# 15A.net
KiCad netlist of a schematic drawn in EasyEDA Pro
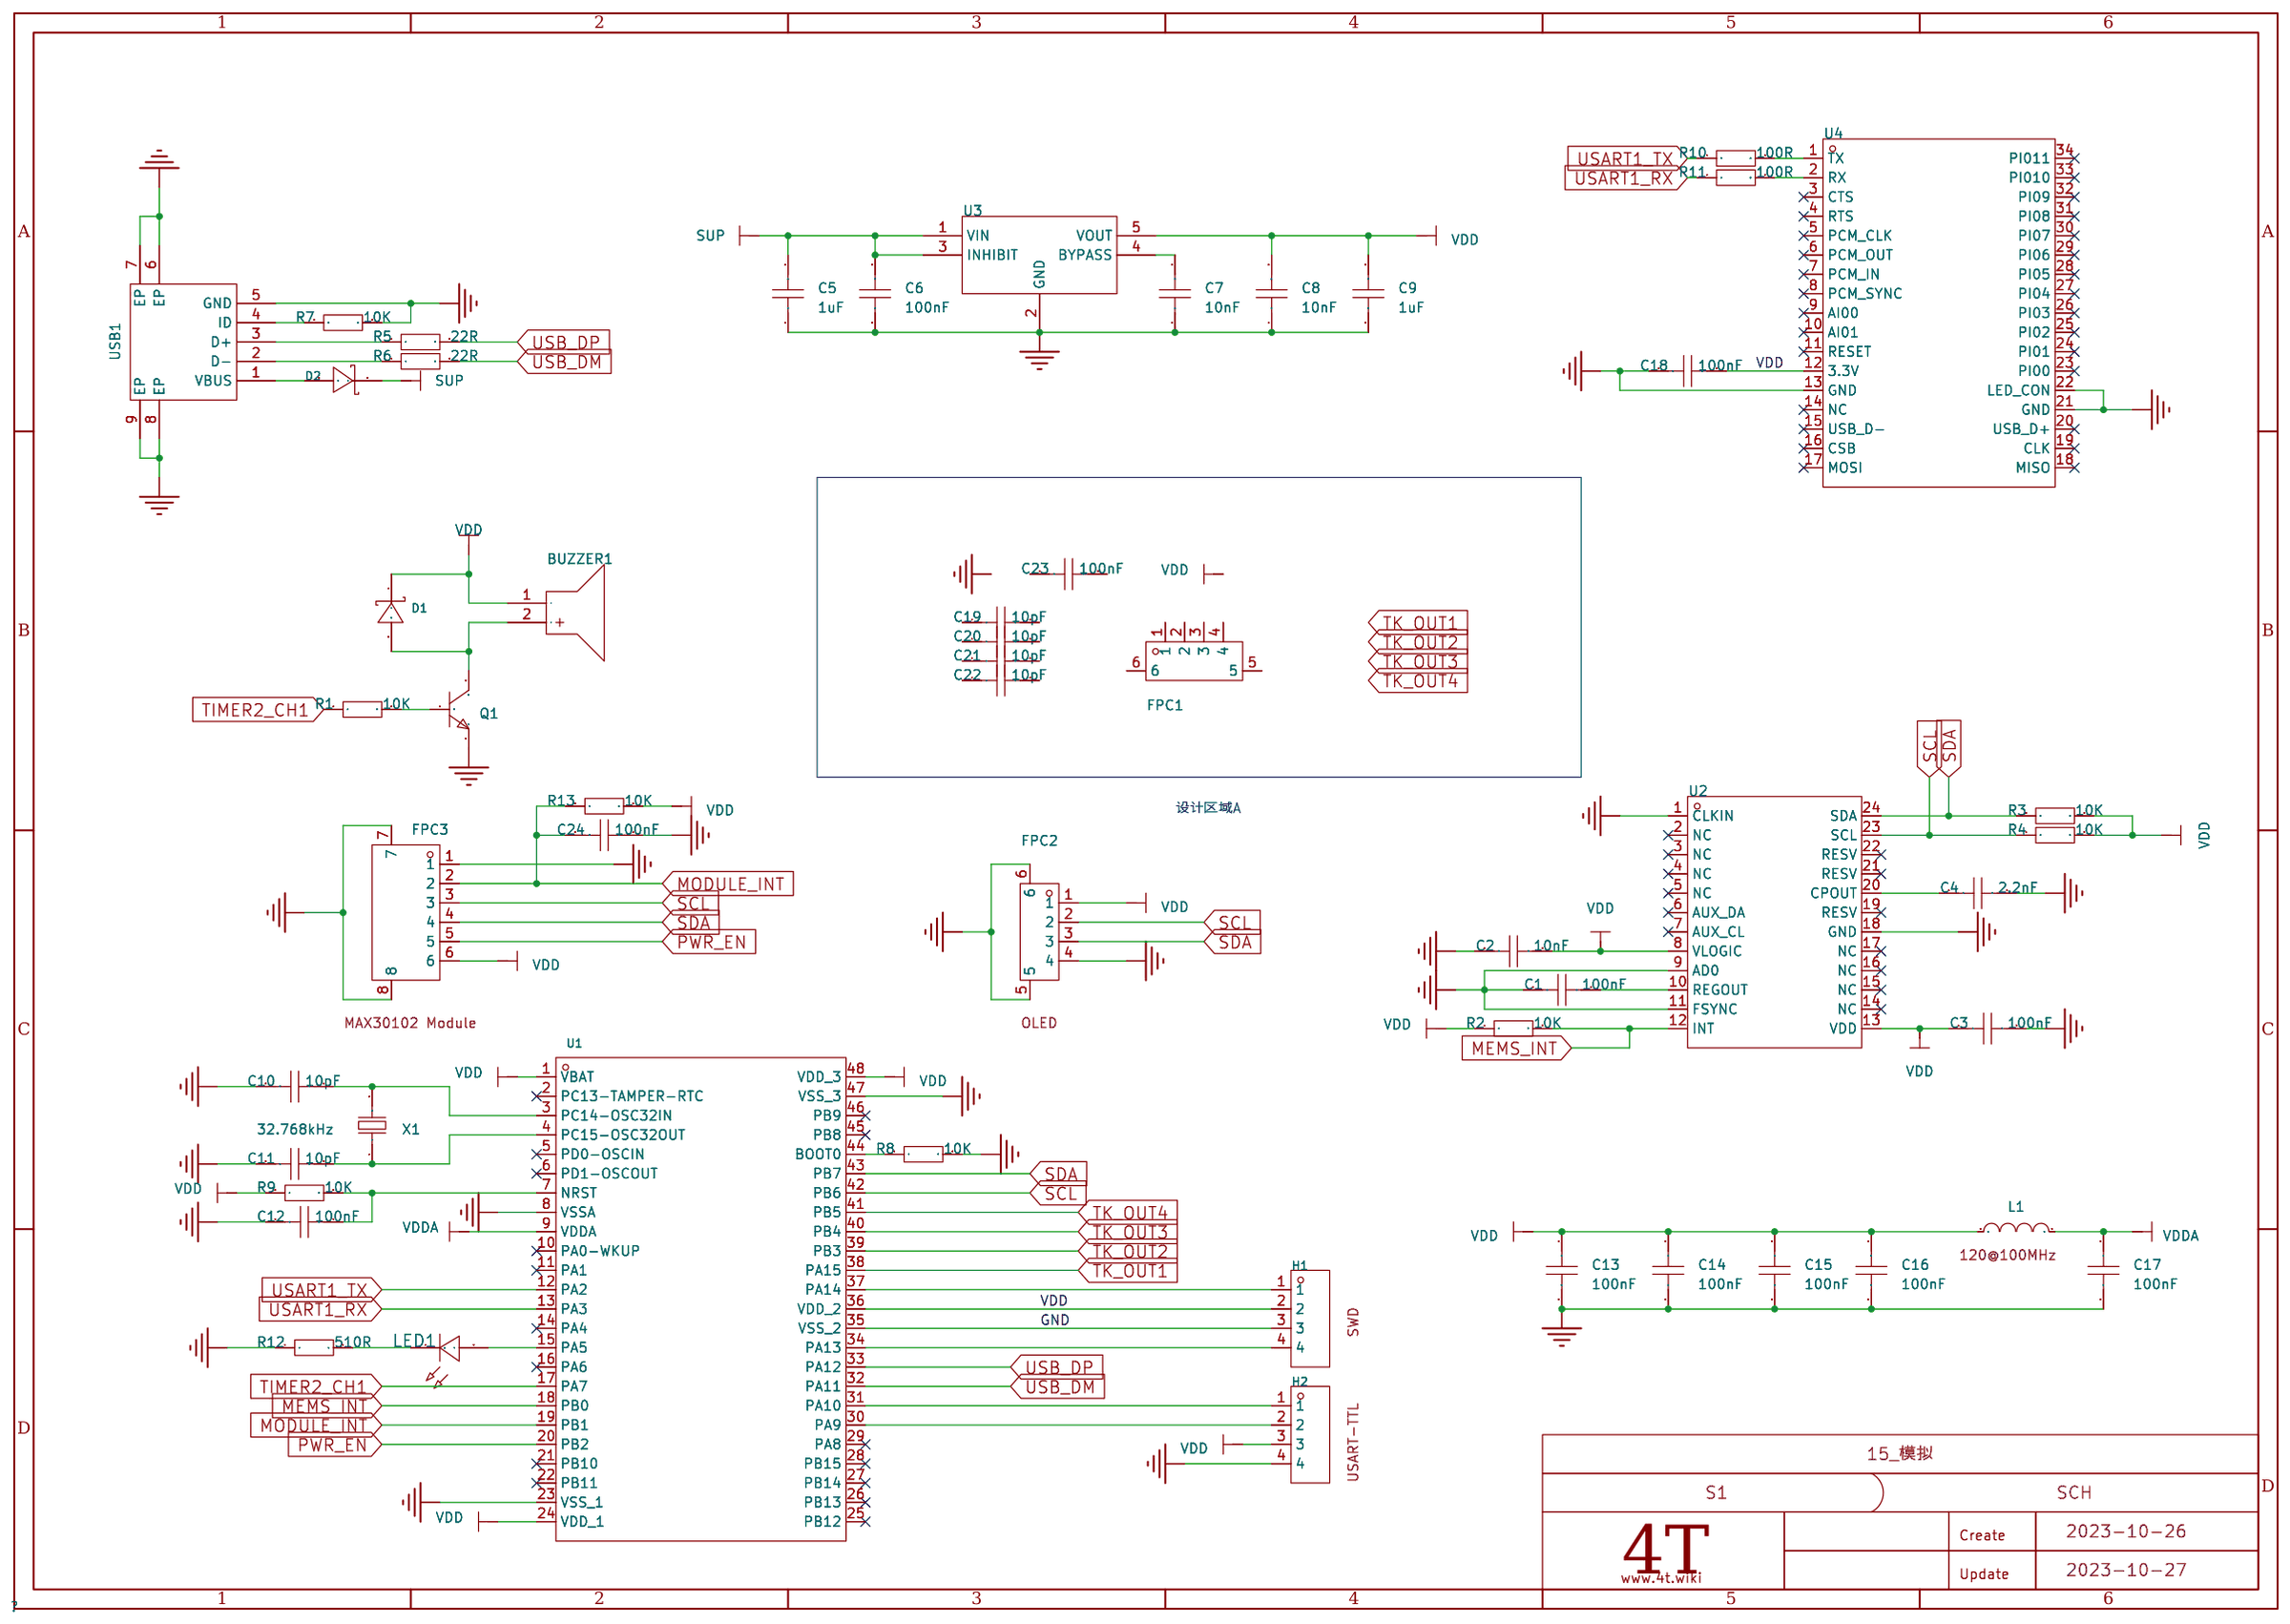
[diagram p0: schematic sheet]

(export (version "E")
  (design (tool "Eeschema 10.0.6"))
  (components
    (comp (ref "BUZZER1")
      (value "buzzer")
      (footprint "easyedapro:BUZ-TH_BD12.0-P6.00-D0.9-RD")
      (libsource (lib "easyedapro") (part "BUZZER"))
    )
    (comp (ref "C1")
      (value "100nF")
      (footprint "easyedapro:C0805")
      (libsource (lib "easyedapro") (part "CapAcitance"))
    )
    (comp (ref "C2")
      (value "10nF")
      (footprint "easyedapro:C0805")
      (libsource (lib "easyedapro") (part "CapAcitance"))
    )
    (comp (ref "C3")
      (value "100nF")
      (footprint "easyedapro:C0805")
      (libsource (lib "easyedapro") (part "CapAcitance"))
    )
    (comp (ref "C4")
      (value "2.2nF")
      (footprint "easyedapro:C0805")
      (libsource (lib "easyedapro") (part "CapAcitance"))
    )
    (comp (ref "C5")
      (value "1uF")
      (footprint "easyedapro:C0805")
      (libsource (lib "easyedapro") (part "CapAcitance"))
    )
    (comp (ref "C6")
      (value "100nF")
      (footprint "easyedapro:C0805")
      (libsource (lib "easyedapro") (part "CapAcitance"))
    )
    (comp (ref "C7")
      (value "10nF")
      (footprint "easyedapro:C0805")
      (libsource (lib "easyedapro") (part "CapAcitance"))
    )
    (comp (ref "C8")
      (value "10nF")
      (footprint "easyedapro:C0805")
      (libsource (lib "easyedapro") (part "CapAcitance"))
    )
    (comp (ref "C9")
      (value "1uF")
      (footprint "easyedapro:C0805")
      (libsource (lib "easyedapro") (part "CapAcitance"))
    )
    (comp (ref "C10")
      (value "10pF")
      (footprint "easyedapro:C0805")
      (libsource (lib "easyedapro") (part "CapAcitance"))
    )
    (comp (ref "C11")
      (value "10pF")
      (footprint "easyedapro:C0805")
      (libsource (lib "easyedapro") (part "CapAcitance"))
    )
    (comp (ref "C12")
      (value "100nF")
      (footprint "easyedapro:C0805")
      (libsource (lib "easyedapro") (part "CapAcitance"))
    )
    (comp (ref "C13")
      (value "100nF")
      (footprint "easyedapro:C0805")
      (libsource (lib "easyedapro") (part "CapAcitance"))
    )
    (comp (ref "C14")
      (value "100nF")
      (footprint "easyedapro:C0805")
      (libsource (lib "easyedapro") (part "CapAcitance"))
    )
    (comp (ref "C15")
      (value "100nF")
      (footprint "easyedapro:C0805")
      (libsource (lib "easyedapro") (part "CapAcitance"))
    )
    (comp (ref "C16")
      (value "100nF")
      (footprint "easyedapro:C0805")
      (libsource (lib "easyedapro") (part "CapAcitance"))
    )
    (comp (ref "C17")
      (value "100nF")
      (footprint "easyedapro:C0805")
      (libsource (lib "easyedapro") (part "CapAcitance"))
    )
    (comp (ref "C18")
      (value "100nF")
      (footprint "easyedapro:C0805")
      (libsource (lib "easyedapro") (part "CapAcitance"))
    )
    (comp (ref "C19")
      (value "10pF")
      (footprint "easyedapro:C0805")
      (libsource (lib "easyedapro") (part "CapAcitance"))
    )
    (comp (ref "C20")
      (value "10pF")
      (footprint "easyedapro:C0805")
      (libsource (lib "easyedapro") (part "CapAcitance"))
    )
    (comp (ref "C21")
      (value "10pF")
      (footprint "easyedapro:C0805")
      (libsource (lib "easyedapro") (part "CapAcitance"))
    )
    (comp (ref "C22")
      (value "10pF")
      (footprint "easyedapro:C0805")
      (libsource (lib "easyedapro") (part "CapAcitance"))
    )
    (comp (ref "C23")
      (value "100nF")
      (footprint "easyedapro:C0805")
      (libsource (lib "easyedapro") (part "CapAcitance"))
    )
    (comp (ref "C24")
      (value "100nF")
      (footprint "easyedapro:C0805")
      (libsource (lib "easyedapro") (part "CapAcitance"))
    )
    (comp (ref "D1")
      (value "SS14")
      (footprint "easyedapro:SMA_L4.2-W2.6-LS5.3-RD")
      (description "二极管配置:独立式;直流反向耐压(Vr):40V;平均整流电流(Io):1A;正向压降(Vf):550mV@1A;")
      (fields (field (name "Manufacturer") "MDD"))
      (libsource (lib "easyedapro") (part "SS14"))
    )
    (comp (ref "D2")
      (value "SS14")
      (footprint "easyedapro:SMA_L4.2-W2.6-LS5.3-RD")
      (description "二极管配置:独立式;直流反向耐压(Vr):40V;平均整流电流(Io):1A;正向压降(Vf):550mV@1A;")
      (fields (field (name "Manufacturer") "MDD"))
      (libsource (lib "easyedapro") (part "SS14"))
    )
    (comp (ref "FPC1")
      (value "FPC-4PIN-1.0MM-上接")
      (footprint "easyedapro:FPC-SMD_4P-P1.00_AFA07-S04ECC-00")
      (libsource (lib "easyedapro") (part "FPC-4PIN-1.0MM-上接"))
    )
    (comp (ref "FPC2")
      (value "FPC-4PIN-1.0MM-上接")
      (footprint "easyedapro:FPC-SMD_4P-P1.00_AFA07-S04ECC-00")
      (description "OLED")
      (libsource (lib "easyedapro") (part "FPC-4PIN-1.0MM-上接"))
    )
    (comp (ref "FPC3")
      (value "FPC6-0.5mm")
      (footprint "easyedapro:FPC-SMD_6P-L9.3-W4.1-P0.50")
      (description "MAX30102 Module")
      (libsource (lib "easyedapro") (part "FPC6-0.5MM"))
    )
    (comp (ref "H1")
      (value "~")
      (footprint "easyedapro:HDR-TH_4P-P2.54-V-F")
      (description "SWD")
      (libsource (lib "easyedapro") (part "2.54-1*4P母"))
    )
    (comp (ref "H2")
      (value "~")
      (footprint "easyedapro:HDR-TH_4P-P2.54-V-F")
      (description "USART-TTL")
      (libsource (lib "easyedapro") (part "2.54-1*4P母"))
    )
    (comp (ref "L1")
      (value "ACMS201209A6012A")
      (footprint "easyedapro:L0805")
      (description "120@100MHz")
      (fields (field (name "Manufacturer") "HYHONGYEX(宏业)"))
      (libsource (lib "easyedapro") (part "ACMS201209A6012A"))
    )
    (comp (ref "LED1")
      (value "~")
      (footprint "easyedapro:LED_0805")
      (libsource (lib "easyedapro") (part "LED_R"))
    )
    (comp (ref "Q1")
      (value "S8050")
      (footprint "easyedapro:SOT-23-3_L2.9-W1.3-P1.90-LS2.4-BR")
      (description "NPN 25V 500mA 120-400 SOT-23")
      (fields (field (name "Manufacturer") "Doeshare(德芯)"))
      (libsource (lib "easyedapro") (part "S8050_C2931719"))
    )
    (comp (ref "R1") (value "10K") (footprint "easyedapro:R0805") (libsource (lib "easyedapro") (part "电阻")))
    (comp (ref "R2") (value "10K") (footprint "easyedapro:R0805") (libsource (lib "easyedapro") (part "电阻")))
    (comp (ref "R3") (value "10K") (footprint "easyedapro:R0805") (libsource (lib "easyedapro") (part "电阻")))
    (comp (ref "R4") (value "10K") (footprint "easyedapro:R0805") (libsource (lib "easyedapro") (part "电阻")))
    (comp (ref "R5") (value "22R") (footprint "easyedapro:R0805") (libsource (lib "easyedapro") (part "电阻")))
    (comp (ref "R6") (value "22R") (footprint "easyedapro:R0805") (libsource (lib "easyedapro") (part "电阻")))
    (comp (ref "R7") (value "10K") (footprint "easyedapro:R0805") (libsource (lib "easyedapro") (part "电阻")))
    (comp (ref "R8") (value "10K") (footprint "easyedapro:R0805") (libsource (lib "easyedapro") (part "电阻")))
    (comp (ref "R9") (value "10K") (footprint "easyedapro:R0805") (libsource (lib "easyedapro") (part "电阻")))
    (comp (ref "R10")
      (value "100R")
      (footprint "easyedapro:R0805")
      (libsource (lib "easyedapro") (part "电阻"))
    )
    (comp (ref "R11")
      (value "100R")
      (footprint "easyedapro:R0805")
      (libsource (lib "easyedapro") (part "电阻"))
    )
    (comp (ref "R12")
      (value "510R")
      (footprint "easyedapro:R0805")
      (libsource (lib "easyedapro") (part "电阻"))
    )
    (comp (ref "R13") (value "10K") (footprint "easyedapro:R0805") (libsource (lib "easyedapro") (part "电阻")))
    (comp (ref "U1")
      (value "GD32F303CBT6")
      (footprint "easyedapro:LQFP-48_L7.0-W7.0-P0.50-LS9.0-BL")
      (libsource (lib "easyedapro") (part "GD32F303CBT6_C3013781"))
    )
    (comp (ref "U2")
      (value "MPU6050")
      (footprint "easyedapro:QFN-24_L4.0-W4.0-P0.50-BL")
      (libsource (lib "easyedapro") (part "MPU6050_C9900042518"))
    )
    (comp (ref "U3")
      (value "LD3985M33R")
      (footprint "easyedapro:SOT-23-5_L3.0-W1.7-P0.95-LS2.8-BR")
      (description "输出类型:固定;输出极性:正;最大输入电压:6V;输出电压:3.3V;输出电流:150mA;电源纹波抑制比(PSRR):60dB;")
      (fields (field (name "Manufacturer") "ST(意法半导体)"))
      (libsource (lib "easyedapro") (part "LD3985M33R"))
    )
    (comp (ref "U4")
      (value "HC-05")
      (footprint "easyedapro:BULETM-SMD_HC-05")
      (libsource (lib "easyedapro") (part "HC-05"))
    )
    (comp (ref "USB1")
      (value "MicroUSB-5PIN")
      (footprint "easyedapro:USB-SMD_5P_MICROUSB-5PIN")
      (libsource (lib "easyedapro") (part "MICROUSB-5PIN"))
    )
    (comp (ref "X1")
      (value "32.768kHz")
      (footprint "easyedapro:FC-135R_L3.2-W1.5")
      (description "频率:32.768kHz;频率公差:±20ppm;负载电容:12.5pF;")
      (fields (field (name "Manufacturer Part") "Q13FC1350000400") (field (name "Manufacturer") "EPSON(爱普生)"))
      (libsource (lib "easyedapro") (part "Q13FC1350000400"))
    )
  )
  (nets
    (net (code "1") (name "GND") (class "Default")
      (node (ref "C1") (pin "1") (pinfunction "1_1") (pintype "input"))
      (node (ref "C10") (pin "2") (pinfunction "2_2") (pintype "input"))
      (node (ref "C11") (pin "2") (pinfunction "2_2") (pintype "input"))
      (node (ref "C12") (pin "2") (pinfunction "2_2") (pintype "input"))
      (node (ref "C13") (pin "2") (pinfunction "2_2") (pintype "input"))
      (node (ref "C14") (pin "2") (pinfunction "2_2") (pintype "input"))
      (node (ref "C15") (pin "2") (pinfunction "2_2") (pintype "input"))
      (node (ref "C16") (pin "2") (pinfunction "2_2") (pintype "input"))
      (node (ref "C17") (pin "2") (pinfunction "2_2") (pintype "input"))
      (node (ref "C18") (pin "1") (pinfunction "1_1") (pintype "input"))
      (node (ref "C2") (pin "1") (pinfunction "1_1") (pintype "input"))
      (node (ref "C24") (pin "1") (pinfunction "1_1") (pintype "input"))
      (node (ref "C3") (pin "2") (pinfunction "2_2") (pintype "input"))
      (node (ref "C4") (pin "2") (pinfunction "2_2") (pintype "input"))
      (node (ref "C5") (pin "1") (pinfunction "1_1") (pintype "input"))
      (node (ref "C6") (pin "1") (pinfunction "1_1") (pintype "input"))
      (node (ref "C7") (pin "1") (pinfunction "1_1") (pintype "input"))
      (node (ref "C8") (pin "1") (pinfunction "1_1") (pintype "input"))
      (node (ref "C9") (pin "1") (pinfunction "1_1") (pintype "input"))
      (node (ref "FPC2") (pin "4") (pinfunction "4_4") (pintype "input"))
      (node (ref "FPC2") (pin "5") (pinfunction "5_5") (pintype "input"))
      (node (ref "FPC2") (pin "6") (pinfunction "6_6") (pintype "input"))
      (node (ref "FPC3") (pin "1") (pinfunction "1_1") (pintype "input"))
      (node (ref "FPC3") (pin "7") (pinfunction "7_7") (pintype "input"))
      (node (ref "FPC3") (pin "8") (pinfunction "8_8") (pintype "input"))
      (node (ref "H1") (pin "3") (pinfunction "3_3") (pintype "input"))
      (node (ref "H2") (pin "4") (pinfunction "4_4") (pintype "input"))
      (node (ref "Q1") (pin "2") (pinfunction "E_2") (pintype "input"))
      (node (ref "R12") (pin "1") (pinfunction "1_1") (pintype "input"))
      (node (ref "R7") (pin "2") (pinfunction "2_2") (pintype "input"))
      (node (ref "R8") (pin "2") (pinfunction "2_2") (pintype "input"))
      (node (ref "U1") (pin "23") (pinfunction "VSS_1_23") (pintype "input"))
      (node (ref "U1") (pin "35") (pinfunction "VSS_2_35") (pintype "input"))
      (node (ref "U1") (pin "47") (pinfunction "VSS_3_47") (pintype "input"))
      (node (ref "U1") (pin "8") (pinfunction "VSSA_8") (pintype "input"))
      (node (ref "U2") (pin "1") (pinfunction "CLKIN_1") (pintype "input"))
      (node (ref "U2") (pin "11") (pinfunction "FSYNC_11") (pintype "input"))
      (node (ref "U2") (pin "18") (pinfunction "GND_18") (pintype "input"))
      (node (ref "U2") (pin "9") (pinfunction "AD0_9") (pintype "input"))
      (node (ref "U3") (pin "2") (pinfunction "GND_2") (pintype "unspecified"))
      (node (ref "U4") (pin "13") (pinfunction "GND_13") (pintype "input"))
      (node (ref "U4") (pin "21") (pinfunction "GND_21") (pintype "input"))
      (node (ref "U4") (pin "22") (pinfunction "LED_CON_22") (pintype "input"))
      (node (ref "USB1") (pin "5") (pinfunction "GND_5") (pintype "input"))
      (node (ref "USB1") (pin "6") (pinfunction "EP_6") (pintype "input"))
      (node (ref "USB1") (pin "7") (pinfunction "EP_7") (pintype "input"))
      (node (ref "USB1") (pin "8") (pinfunction "EP_8") (pintype "input"))
      (node (ref "USB1") (pin "9") (pinfunction "EP_9") (pintype "input"))
    )
    (net (code "2") (name "MEMS_INT") (class "Default")
      (node (ref "R2") (pin "2") (pinfunction "2_2") (pintype "input"))
      (node (ref "U1") (pin "18") (pinfunction "PB0_18") (pintype "input"))
      (node (ref "U2") (pin "12") (pinfunction "INT_12") (pintype "input"))
    )
    (net (code "3") (name "MODULE_INT") (class "Default")
      (node (ref "C24") (pin "2") (pinfunction "2_2") (pintype "input"))
      (node (ref "FPC3") (pin "2") (pinfunction "2_2") (pintype "input"))
      (node (ref "R13") (pin "1") (pinfunction "1_1") (pintype "input"))
      (node (ref "U1") (pin "19") (pinfunction "PB1_19") (pintype "input"))
    )
    (net (code "4") (name "Net-(BUZZER1-+)") (class "Default")
      (node (ref "BUZZER1") (pin "2") (pinfunction "+_2") (pintype "input"))
      (node (ref "D1") (pin "2") (pinfunction "A_2") (pintype "input"))
      (node (ref "Q1") (pin "3") (pinfunction "C_3") (pintype "input"))
    )
    (net (code "5") (name "Net-(D2-A)") (class "Default")
      (node (ref "D2") (pin "2") (pinfunction "A_2") (pintype "input"))
      (node (ref "USB1") (pin "1") (pinfunction "VBUS_1") (pintype "input"))
    )
    (net (code "6") (name "Net-(LED1-A)") (class "Default")
      (node (ref "LED1") (pin "2") (pinfunction "A_2") (pintype "input"))
      (node (ref "U1") (pin "15") (pinfunction "PA5_15") (pintype "input"))
    )
    (net (code "7") (name "Net-(LED1-C)") (class "Default")
      (node (ref "LED1") (pin "1") (pinfunction "C_1") (pintype "input"))
      (node (ref "R12") (pin "2") (pinfunction "2_2") (pintype "input"))
    )
    (net (code "8") (name "Net-(Q1-B)") (class "Default")
      (node (ref "Q1") (pin "1") (pinfunction "B_1") (pintype "input"))
      (node (ref "R1") (pin "2") (pinfunction "2_2") (pintype "input"))
    )
    (net (code "9") (name "Net-(U1-BOOT0)") (class "Default")
      (node (ref "R8") (pin "1") (pinfunction "1_1") (pintype "input"))
      (node (ref "U1") (pin "44") (pinfunction "BOOT0_44") (pintype "input"))
    )
    (net (code "10") (name "Net-(U1-NRST)") (class "Default")
      (node (ref "C12") (pin "1") (pinfunction "1_1") (pintype "input"))
      (node (ref "R9") (pin "2") (pinfunction "2_2") (pintype "input"))
      (node (ref "U1") (pin "7") (pinfunction "NRST_7") (pintype "input"))
    )
    (net (code "11") (name "Net-(U1-PA9)") (class "Default")
      (node (ref "H2") (pin "2") (pinfunction "2_2") (pintype "input"))
      (node (ref "U1") (pin "30") (pinfunction "PA9_30") (pintype "input"))
    )
    (net (code "12") (name "Net-(U1-PA10)") (class "Default")
      (node (ref "H2") (pin "1") (pinfunction "1_1") (pintype "input"))
      (node (ref "U1") (pin "31") (pinfunction "PA10_31") (pintype "input"))
    )
    (net (code "13") (name "Net-(U1-PA13)") (class "Default")
      (node (ref "H1") (pin "4") (pinfunction "4_4") (pintype "input"))
      (node (ref "U1") (pin "34") (pinfunction "PA13_34") (pintype "input"))
    )
    (net (code "14") (name "Net-(U1-PA14)") (class "Default")
      (node (ref "H1") (pin "1") (pinfunction "1_1") (pintype "input"))
      (node (ref "U1") (pin "37") (pinfunction "PA14_37") (pintype "input"))
    )
    (net (code "15") (name "Net-(U1-PC14-OSC32IN)") (class "Default")
      (node (ref "C10") (pin "1") (pinfunction "1_1") (pintype "input"))
      (node (ref "U1") (pin "3") (pinfunction "PC14-OSC32IN_3") (pintype "input"))
      (node (ref "X1") (pin "2") (pinfunction "2_2") (pintype "input"))
    )
    (net (code "16") (name "Net-(U1-PC15-OSC32OUT)") (class "Default")
      (node (ref "C11") (pin "1") (pinfunction "1_1") (pintype "input"))
      (node (ref "U1") (pin "4") (pinfunction "PC15-OSC32OUT_4") (pintype "input"))
      (node (ref "X1") (pin "1") (pinfunction "1_1") (pintype "input"))
    )
    (net (code "17") (name "Net-(U2-CPOUT)") (class "Default")
      (node (ref "C4") (pin "1") (pinfunction "1_1") (pintype "input"))
      (node (ref "U2") (pin "20") (pinfunction "CPOUT_20") (pintype "input"))
    )
    (net (code "18") (name "Net-(U2-REGOUT)") (class "Default")
      (node (ref "C1") (pin "2") (pinfunction "2_2") (pintype "input"))
      (node (ref "U2") (pin "10") (pinfunction "REGOUT_10") (pintype "input"))
    )
    (net (code "19") (name "Net-(U3-BYPASS)") (class "Default")
      (node (ref "C7") (pin "2") (pinfunction "2_2") (pintype "input"))
      (node (ref "U3") (pin "4") (pinfunction "BYPASS_4") (pintype "unspecified"))
    )
    (net (code "20") (name "Net-(U4-RX)") (class "Default")
      (node (ref "R11") (pin "2") (pinfunction "2_2") (pintype "input"))
      (node (ref "U4") (pin "2") (pinfunction "RX_2") (pintype "input"))
    )
    (net (code "21") (name "Net-(U4-TX)") (class "Default")
      (node (ref "R10") (pin "2") (pinfunction "2_2") (pintype "input"))
      (node (ref "U4") (pin "1") (pinfunction "TX_1") (pintype "input"))
    )
    (net (code "22") (name "Net-(USB1-D+)") (class "Default")
      (node (ref "R5") (pin "1") (pinfunction "1_1") (pintype "input"))
      (node (ref "USB1") (pin "3") (pinfunction "D+_3") (pintype "input"))
    )
    (net (code "23") (name "Net-(USB1-D-)") (class "Default")
      (node (ref "R6") (pin "1") (pinfunction "1_1") (pintype "input"))
      (node (ref "USB1") (pin "2") (pinfunction "D-_2") (pintype "input"))
    )
    (net (code "24") (name "Net-(USB1-ID)") (class "Default")
      (node (ref "R7") (pin "1") (pinfunction "1_1") (pintype "input"))
      (node (ref "USB1") (pin "4") (pinfunction "ID_4") (pintype "input"))
    )
    (net (code "25") (name "PWR_EN") (class "Default")
      (node (ref "FPC3") (pin "5") (pinfunction "5_5") (pintype "input"))
      (node (ref "U1") (pin "20") (pinfunction "PB2_20") (pintype "input"))
    )
    (net (code "26") (name "SCL") (class "Default")
      (node (ref "FPC2") (pin "2") (pinfunction "2_2") (pintype "input"))
      (node (ref "FPC3") (pin "3") (pinfunction "3_3") (pintype "input"))
      (node (ref "R4") (pin "1") (pinfunction "1_1") (pintype "input"))
      (node (ref "U1") (pin "42") (pinfunction "PB6_42") (pintype "input"))
      (node (ref "U2") (pin "23") (pinfunction "SCL_23") (pintype "input"))
    )
    (net (code "27") (name "SDA") (class "Default")
      (node (ref "FPC2") (pin "3") (pinfunction "3_3") (pintype "input"))
      (node (ref "FPC3") (pin "4") (pinfunction "4_4") (pintype "input"))
      (node (ref "R3") (pin "1") (pinfunction "1_1") (pintype "input"))
      (node (ref "U1") (pin "43") (pinfunction "PB7_43") (pintype "input"))
      (node (ref "U2") (pin "24") (pinfunction "SDA_24") (pintype "input"))
    )
    (net (code "28") (name "SUP") (class "Default")
      (node (ref "C5") (pin "2") (pinfunction "2_2") (pintype "input"))
      (node (ref "C6") (pin "2") (pinfunction "2_2") (pintype "input"))
      (node (ref "D2") (pin "1") (pinfunction "K_1") (pintype "input"))
      (node (ref "U3") (pin "1") (pinfunction "VIN_1") (pintype "unspecified"))
      (node (ref "U3") (pin "3") (pinfunction "INHIBIT_3") (pintype "unspecified"))
    )
    (net (code "29") (name "TIMER2_CH1") (class "Default")
      (node (ref "R1") (pin "1") (pinfunction "1_1") (pintype "input"))
      (node (ref "U1") (pin "17") (pinfunction "PA7_17") (pintype "input"))
    )
    (net (code "30") (name "TK_OUT1") (class "Default")
      (node (ref "U1") (pin "38") (pinfunction "PA15_38") (pintype "input"))
    )
    (net (code "31") (name "TK_OUT2") (class "Default")
      (node (ref "U1") (pin "39") (pinfunction "PB3_39") (pintype "input"))
    )
    (net (code "32") (name "TK_OUT3") (class "Default")
      (node (ref "U1") (pin "40") (pinfunction "PB4_40") (pintype "input"))
    )
    (net (code "33") (name "TK_OUT4") (class "Default")
      (node (ref "U1") (pin "41") (pinfunction "PB5_41") (pintype "input"))
    )
    (net (code "34") (name "USART1_RX") (class "Default")
      (node (ref "R11") (pin "1") (pinfunction "1_1") (pintype "input"))
      (node (ref "U1") (pin "13") (pinfunction "PA3_13") (pintype "input"))
    )
    (net (code "35") (name "USART1_TX") (class "Default")
      (node (ref "R10") (pin "1") (pinfunction "1_1") (pintype "input"))
      (node (ref "U1") (pin "12") (pinfunction "PA2_12") (pintype "input"))
    )
    (net (code "36") (name "USB_DM") (class "Default")
      (node (ref "R6") (pin "2") (pinfunction "2_2") (pintype "input"))
      (node (ref "U1") (pin "32") (pinfunction "PA11_32") (pintype "input"))
    )
    (net (code "37") (name "USB_DP") (class "Default")
      (node (ref "R5") (pin "2") (pinfunction "2_2") (pintype "input"))
      (node (ref "U1") (pin "33") (pinfunction "PA12_33") (pintype "input"))
    )
    (net (code "38") (name "VDD") (class "Default")
      (node (ref "BUZZER1") (pin "1") (pinfunction "-_1") (pintype "input"))
      (node (ref "C13") (pin "1") (pinfunction "1_1") (pintype "input"))
      (node (ref "C14") (pin "1") (pinfunction "1_1") (pintype "input"))
      (node (ref "C15") (pin "1") (pinfunction "1_1") (pintype "input"))
      (node (ref "C16") (pin "1") (pinfunction "1_1") (pintype "input"))
      (node (ref "C18") (pin "2") (pinfunction "2_2") (pintype "input"))
      (node (ref "C2") (pin "2") (pinfunction "2_2") (pintype "input"))
      (node (ref "C3") (pin "1") (pinfunction "1_1") (pintype "input"))
      (node (ref "C8") (pin "2") (pinfunction "2_2") (pintype "input"))
      (node (ref "C9") (pin "2") (pinfunction "2_2") (pintype "input"))
      (node (ref "D1") (pin "1") (pinfunction "K_1") (pintype "input"))
      (node (ref "FPC2") (pin "1") (pinfunction "1_1") (pintype "input"))
      (node (ref "FPC3") (pin "6") (pinfunction "6_6") (pintype "input"))
      (node (ref "H1") (pin "2") (pinfunction "2_2") (pintype "input"))
      (node (ref "H2") (pin "3") (pinfunction "3_3") (pintype "input"))
      (node (ref "L1") (pin "1") (pinfunction "1_1") (pintype "input"))
      (node (ref "R13") (pin "2") (pinfunction "2_2") (pintype "input"))
      (node (ref "R2") (pin "1") (pinfunction "1_1") (pintype "input"))
      (node (ref "R3") (pin "2") (pinfunction "2_2") (pintype "input"))
      (node (ref "R4") (pin "2") (pinfunction "2_2") (pintype "input"))
      (node (ref "R9") (pin "1") (pinfunction "1_1") (pintype "input"))
      (node (ref "U1") (pin "1") (pinfunction "VBAT_1") (pintype "input"))
      (node (ref "U1") (pin "24") (pinfunction "VDD_1_24") (pintype "input"))
      (node (ref "U1") (pin "36") (pinfunction "VDD_2_36") (pintype "input"))
      (node (ref "U1") (pin "48") (pinfunction "VDD_3_48") (pintype "input"))
      (node (ref "U2") (pin "13") (pinfunction "VDD_13") (pintype "input"))
      (node (ref "U2") (pin "8") (pinfunction "VLOGIC_8") (pintype "input"))
      (node (ref "U3") (pin "5") (pinfunction "VOUT_5") (pintype "unspecified"))
      (node (ref "U4") (pin "12") (pinfunction "3.3V_12") (pintype "input"))
    )
    (net (code "39") (name "VDDA") (class "Default")
      (node (ref "C17") (pin "1") (pinfunction "1_1") (pintype "input"))
      (node (ref "L1") (pin "2") (pinfunction "2_2") (pintype "input"))
      (node (ref "U1") (pin "9") (pinfunction "VDDA_9") (pintype "input"))
    )
    (net (code "40") (name "unconnected-(C19-Pad1)") (class "Default")
      (node (ref "C19") (pin "1") (pinfunction "1_1") (pintype "input"))
    )
    (net (code "41") (name "unconnected-(C19-Pad2)") (class "Default")
      (node (ref "C19") (pin "2") (pinfunction "2_2") (pintype "input"))
    )
    (net (code "42") (name "unconnected-(C20-Pad1)") (class "Default")
      (node (ref "C20") (pin "1") (pinfunction "1_1") (pintype "input"))
    )
    (net (code "43") (name "unconnected-(C20-Pad2)") (class "Default")
      (node (ref "C20") (pin "2") (pinfunction "2_2") (pintype "input"))
    )
    (net (code "44") (name "unconnected-(C21-Pad1)") (class "Default")
      (node (ref "C21") (pin "1") (pinfunction "1_1") (pintype "input"))
    )
    (net (code "45") (name "unconnected-(C21-Pad2)") (class "Default")
      (node (ref "C21") (pin "2") (pinfunction "2_2") (pintype "input"))
    )
    (net (code "46") (name "unconnected-(C22-Pad1)") (class "Default")
      (node (ref "C22") (pin "1") (pinfunction "1_1") (pintype "input"))
    )
    (net (code "47") (name "unconnected-(C22-Pad2)") (class "Default")
      (node (ref "C22") (pin "2") (pinfunction "2_2") (pintype "input"))
    )
    (net (code "48") (name "unconnected-(C23-Pad1)") (class "Default")
      (node (ref "C23") (pin "1") (pinfunction "1_1") (pintype "input"))
    )
    (net (code "49") (name "unconnected-(C23-Pad2)") (class "Default")
      (node (ref "C23") (pin "2") (pinfunction "2_2") (pintype "input"))
    )
    (net (code "50") (name "unconnected-(FPC1-Pad1)") (class "Default")
      (node (ref "FPC1") (pin "1") (pinfunction "1_1") (pintype "input"))
    )
    (net (code "51") (name "unconnected-(FPC1-Pad2)") (class "Default")
      (node (ref "FPC1") (pin "2") (pinfunction "2_2") (pintype "input"))
    )
    (net (code "52") (name "unconnected-(FPC1-Pad3)") (class "Default")
      (node (ref "FPC1") (pin "3") (pinfunction "3_3") (pintype "input"))
    )
    (net (code "53") (name "unconnected-(FPC1-Pad4)") (class "Default")
      (node (ref "FPC1") (pin "4") (pinfunction "4_4") (pintype "input"))
    )
    (net (code "54") (name "unconnected-(FPC1-Pad5)") (class "Default")
      (node (ref "FPC1") (pin "5") (pinfunction "5_5") (pintype "input"))
    )
    (net (code "55") (name "unconnected-(FPC1-Pad6)") (class "Default")
      (node (ref "FPC1") (pin "6") (pinfunction "6_6") (pintype "input"))
    )
    (net (code "56") (name "unconnected-(U1-PA0-WKUP-Pad10)") (class "Default")
      (node (ref "U1") (pin "10") (pinfunction "PA0-WKUP_10") (pintype "input+no_connect"))
    )
    (net (code "57") (name "unconnected-(U1-PA1-Pad11)") (class "Default")
      (node (ref "U1") (pin "11") (pinfunction "PA1_11") (pintype "input+no_connect"))
    )
    (net (code "58") (name "unconnected-(U1-PA4-Pad14)") (class "Default")
      (node (ref "U1") (pin "14") (pinfunction "PA4_14") (pintype "input+no_connect"))
    )
    (net (code "59") (name "unconnected-(U1-PA6-Pad16)") (class "Default")
      (node (ref "U1") (pin "16") (pinfunction "PA6_16") (pintype "input+no_connect"))
    )
    (net (code "60") (name "unconnected-(U1-PA8-Pad29)") (class "Default")
      (node (ref "U1") (pin "29") (pinfunction "PA8_29") (pintype "input+no_connect"))
    )
    (net (code "61") (name "unconnected-(U1-PB8-Pad45)") (class "Default")
      (node (ref "U1") (pin "45") (pinfunction "PB8_45") (pintype "input+no_connect"))
    )
    (net (code "62") (name "unconnected-(U1-PB9-Pad46)") (class "Default")
      (node (ref "U1") (pin "46") (pinfunction "PB9_46") (pintype "input+no_connect"))
    )
    (net (code "63") (name "unconnected-(U1-PB10-Pad21)") (class "Default")
      (node (ref "U1") (pin "21") (pinfunction "PB10_21") (pintype "input+no_connect"))
    )
    (net (code "64") (name "unconnected-(U1-PB11-Pad22)") (class "Default")
      (node (ref "U1") (pin "22") (pinfunction "PB11_22") (pintype "input+no_connect"))
    )
    (net (code "65") (name "unconnected-(U1-PB12-Pad25)") (class "Default")
      (node (ref "U1") (pin "25") (pinfunction "PB12_25") (pintype "input+no_connect"))
    )
    (net (code "66") (name "unconnected-(U1-PB13-Pad26)") (class "Default")
      (node (ref "U1") (pin "26") (pinfunction "PB13_26") (pintype "input+no_connect"))
    )
    (net (code "67") (name "unconnected-(U1-PB14-Pad27)") (class "Default")
      (node (ref "U1") (pin "27") (pinfunction "PB14_27") (pintype "input+no_connect"))
    )
    (net (code "68") (name "unconnected-(U1-PB15-Pad28)") (class "Default")
      (node (ref "U1") (pin "28") (pinfunction "PB15_28") (pintype "input+no_connect"))
    )
    (net (code "69") (name "unconnected-(U1-PC13-TAMPER-RTC-Pad2)") (class "Default")
      (node (ref "U1") (pin "2") (pinfunction "PC13-TAMPER-RTC_2") (pintype "input+no_connect"))
    )
    (net (code "70") (name "unconnected-(U1-PD0-OSCIN-Pad5)") (class "Default")
      (node (ref "U1") (pin "5") (pinfunction "PD0-OSCIN_5") (pintype "input+no_connect"))
    )
    (net (code "71") (name "unconnected-(U1-PD1-OSCOUT-Pad6)") (class "Default")
      (node (ref "U1") (pin "6") (pinfunction "PD1-OSCOUT_6") (pintype "input+no_connect"))
    )
    (net (code "72") (name "unconnected-(U2-AUX_CL-Pad7)") (class "Default")
      (node (ref "U2") (pin "7") (pinfunction "AUX_CL_7") (pintype "input+no_connect"))
    )
    (net (code "73") (name "unconnected-(U2-AUX_DA-Pad6)") (class "Default")
      (node (ref "U2") (pin "6") (pinfunction "AUX_DA_6") (pintype "input+no_connect"))
    )
    (net (code "74") (name "unconnected-(U2-NC-Pad2)") (class "Default")
      (node (ref "U2") (pin "2") (pinfunction "NC_2") (pintype "input+no_connect"))
    )
    (net (code "75") (name "unconnected-(U2-NC-Pad3)") (class "Default")
      (node (ref "U2") (pin "3") (pinfunction "NC_3") (pintype "input+no_connect"))
    )
    (net (code "76") (name "unconnected-(U2-NC-Pad4)") (class "Default")
      (node (ref "U2") (pin "4") (pinfunction "NC_4") (pintype "input+no_connect"))
    )
    (net (code "77") (name "unconnected-(U2-NC-Pad5)") (class "Default")
      (node (ref "U2") (pin "5") (pinfunction "NC_5") (pintype "input+no_connect"))
    )
    (net (code "78") (name "unconnected-(U2-NC-Pad14)") (class "Default")
      (node (ref "U2") (pin "14") (pinfunction "NC_14") (pintype "input+no_connect"))
    )
    (net (code "79") (name "unconnected-(U2-NC-Pad15)") (class "Default")
      (node (ref "U2") (pin "15") (pinfunction "NC_15") (pintype "input+no_connect"))
    )
    (net (code "80") (name "unconnected-(U2-NC-Pad16)") (class "Default")
      (node (ref "U2") (pin "16") (pinfunction "NC_16") (pintype "input+no_connect"))
    )
    (net (code "81") (name "unconnected-(U2-NC-Pad17)") (class "Default")
      (node (ref "U2") (pin "17") (pinfunction "NC_17") (pintype "input+no_connect"))
    )
    (net (code "82") (name "unconnected-(U2-RESV-Pad19)") (class "Default")
      (node (ref "U2") (pin "19") (pinfunction "RESV_19") (pintype "input+no_connect"))
    )
    (net (code "83") (name "unconnected-(U2-RESV-Pad21)") (class "Default")
      (node (ref "U2") (pin "21") (pinfunction "RESV_21") (pintype "input+no_connect"))
    )
    (net (code "84") (name "unconnected-(U2-RESV-Pad22)") (class "Default")
      (node (ref "U2") (pin "22") (pinfunction "RESV_22") (pintype "input+no_connect"))
    )
    (net (code "85") (name "unconnected-(U4-AI00-Pad9)") (class "Default")
      (node (ref "U4") (pin "9") (pinfunction "AI00_9") (pintype "input+no_connect"))
    )
    (net (code "86") (name "unconnected-(U4-AI01-Pad10)") (class "Default")
      (node (ref "U4") (pin "10") (pinfunction "AI01_10") (pintype "input+no_connect"))
    )
    (net (code "87") (name "unconnected-(U4-CLK-Pad19)") (class "Default")
      (node (ref "U4") (pin "19") (pinfunction "CLK_19") (pintype "input+no_connect"))
    )
    (net (code "88") (name "unconnected-(U4-CSB-Pad16)") (class "Default")
      (node (ref "U4") (pin "16") (pinfunction "CSB_16") (pintype "input+no_connect"))
    )
    (net (code "89") (name "unconnected-(U4-CTS-Pad3)") (class "Default")
      (node (ref "U4") (pin "3") (pinfunction "CTS_3") (pintype "input+no_connect"))
    )
    (net (code "90") (name "unconnected-(U4-MISO-Pad18)") (class "Default")
      (node (ref "U4") (pin "18") (pinfunction "MISO_18") (pintype "input+no_connect"))
    )
    (net (code "91") (name "unconnected-(U4-MOSI-Pad17)") (class "Default")
      (node (ref "U4") (pin "17") (pinfunction "MOSI_17") (pintype "input+no_connect"))
    )
    (net (code "92") (name "unconnected-(U4-NC-Pad14)") (class "Default")
      (node (ref "U4") (pin "14") (pinfunction "NC_14") (pintype "input+no_connect"))
    )
    (net (code "93") (name "unconnected-(U4-PCM_CLK-Pad5)") (class "Default")
      (node (ref "U4") (pin "5") (pinfunction "PCM_CLK_5") (pintype "input+no_connect"))
    )
    (net (code "94") (name "unconnected-(U4-PCM_IN-Pad7)") (class "Default")
      (node (ref "U4") (pin "7") (pinfunction "PCM_IN_7") (pintype "input+no_connect"))
    )
    (net (code "95") (name "unconnected-(U4-PCM_OUT-Pad6)") (class "Default")
      (node (ref "U4") (pin "6") (pinfunction "PCM_OUT_6") (pintype "input+no_connect"))
    )
    (net (code "96") (name "unconnected-(U4-PCM_SYNC-Pad8)") (class "Default")
      (node (ref "U4") (pin "8") (pinfunction "PCM_SYNC_8") (pintype "input+no_connect"))
    )
    (net (code "97") (name "unconnected-(U4-PI00-Pad23)") (class "Default")
      (node (ref "U4") (pin "23") (pinfunction "PI00_23") (pintype "input+no_connect"))
    )
    (net (code "98") (name "unconnected-(U4-PI01-Pad24)") (class "Default")
      (node (ref "U4") (pin "24") (pinfunction "PI01_24") (pintype "input+no_connect"))
    )
    (net (code "99") (name "unconnected-(U4-PI02-Pad25)") (class "Default")
      (node (ref "U4") (pin "25") (pinfunction "PI02_25") (pintype "input+no_connect"))
    )
    (net (code "100") (name "unconnected-(U4-PI03-Pad26)") (class "Default")
      (node (ref "U4") (pin "26") (pinfunction "PI03_26") (pintype "input+no_connect"))
    )
    (net (code "101") (name "unconnected-(U4-PI04-Pad27)") (class "Default")
      (node (ref "U4") (pin "27") (pinfunction "PI04_27") (pintype "input+no_connect"))
    )
    (net (code "102") (name "unconnected-(U4-PI05-Pad28)") (class "Default")
      (node (ref "U4") (pin "28") (pinfunction "PI05_28") (pintype "input+no_connect"))
    )
    (net (code "103") (name "unconnected-(U4-PI06-Pad29)") (class "Default")
      (node (ref "U4") (pin "29") (pinfunction "PI06_29") (pintype "input+no_connect"))
    )
    (net (code "104") (name "unconnected-(U4-PI07-Pad30)") (class "Default")
      (node (ref "U4") (pin "30") (pinfunction "PI07_30") (pintype "input+no_connect"))
    )
    (net (code "105") (name "unconnected-(U4-PI08-Pad31)") (class "Default")
      (node (ref "U4") (pin "31") (pinfunction "PI08_31") (pintype "input+no_connect"))
    )
    (net (code "106") (name "unconnected-(U4-PI09-Pad32)") (class "Default")
      (node (ref "U4") (pin "32") (pinfunction "PI09_32") (pintype "input+no_connect"))
    )
    (net (code "107") (name "unconnected-(U4-PI010-Pad33)") (class "Default")
      (node (ref "U4") (pin "33") (pinfunction "PI010_33") (pintype "input+no_connect"))
    )
    (net (code "108") (name "unconnected-(U4-PI011-Pad34)") (class "Default")
      (node (ref "U4") (pin "34") (pinfunction "PI011_34") (pintype "input+no_connect"))
    )
    (net (code "109") (name "unconnected-(U4-RESET-Pad11)") (class "Default")
      (node (ref "U4") (pin "11") (pinfunction "RESET_11") (pintype "input+no_connect"))
    )
    (net (code "110") (name "unconnected-(U4-RTS-Pad4)") (class "Default")
      (node (ref "U4") (pin "4") (pinfunction "RTS_4") (pintype "input+no_connect"))
    )
    (net (code "111") (name "unconnected-(U4-USB_D+-Pad20)") (class "Default")
      (node (ref "U4") (pin "20") (pinfunction "USB_D+_20") (pintype "input+no_connect"))
    )
    (net (code "112") (name "unconnected-(U4-USB_D--Pad15)") (class "Default")
      (node (ref "U4") (pin "15") (pinfunction "USB_D-_15") (pintype "input+no_connect"))
    )
  )
)
